# Isolated_I2C_Bus_Repeater.net
KiCad netlist of a schematic drawn in EAGLE
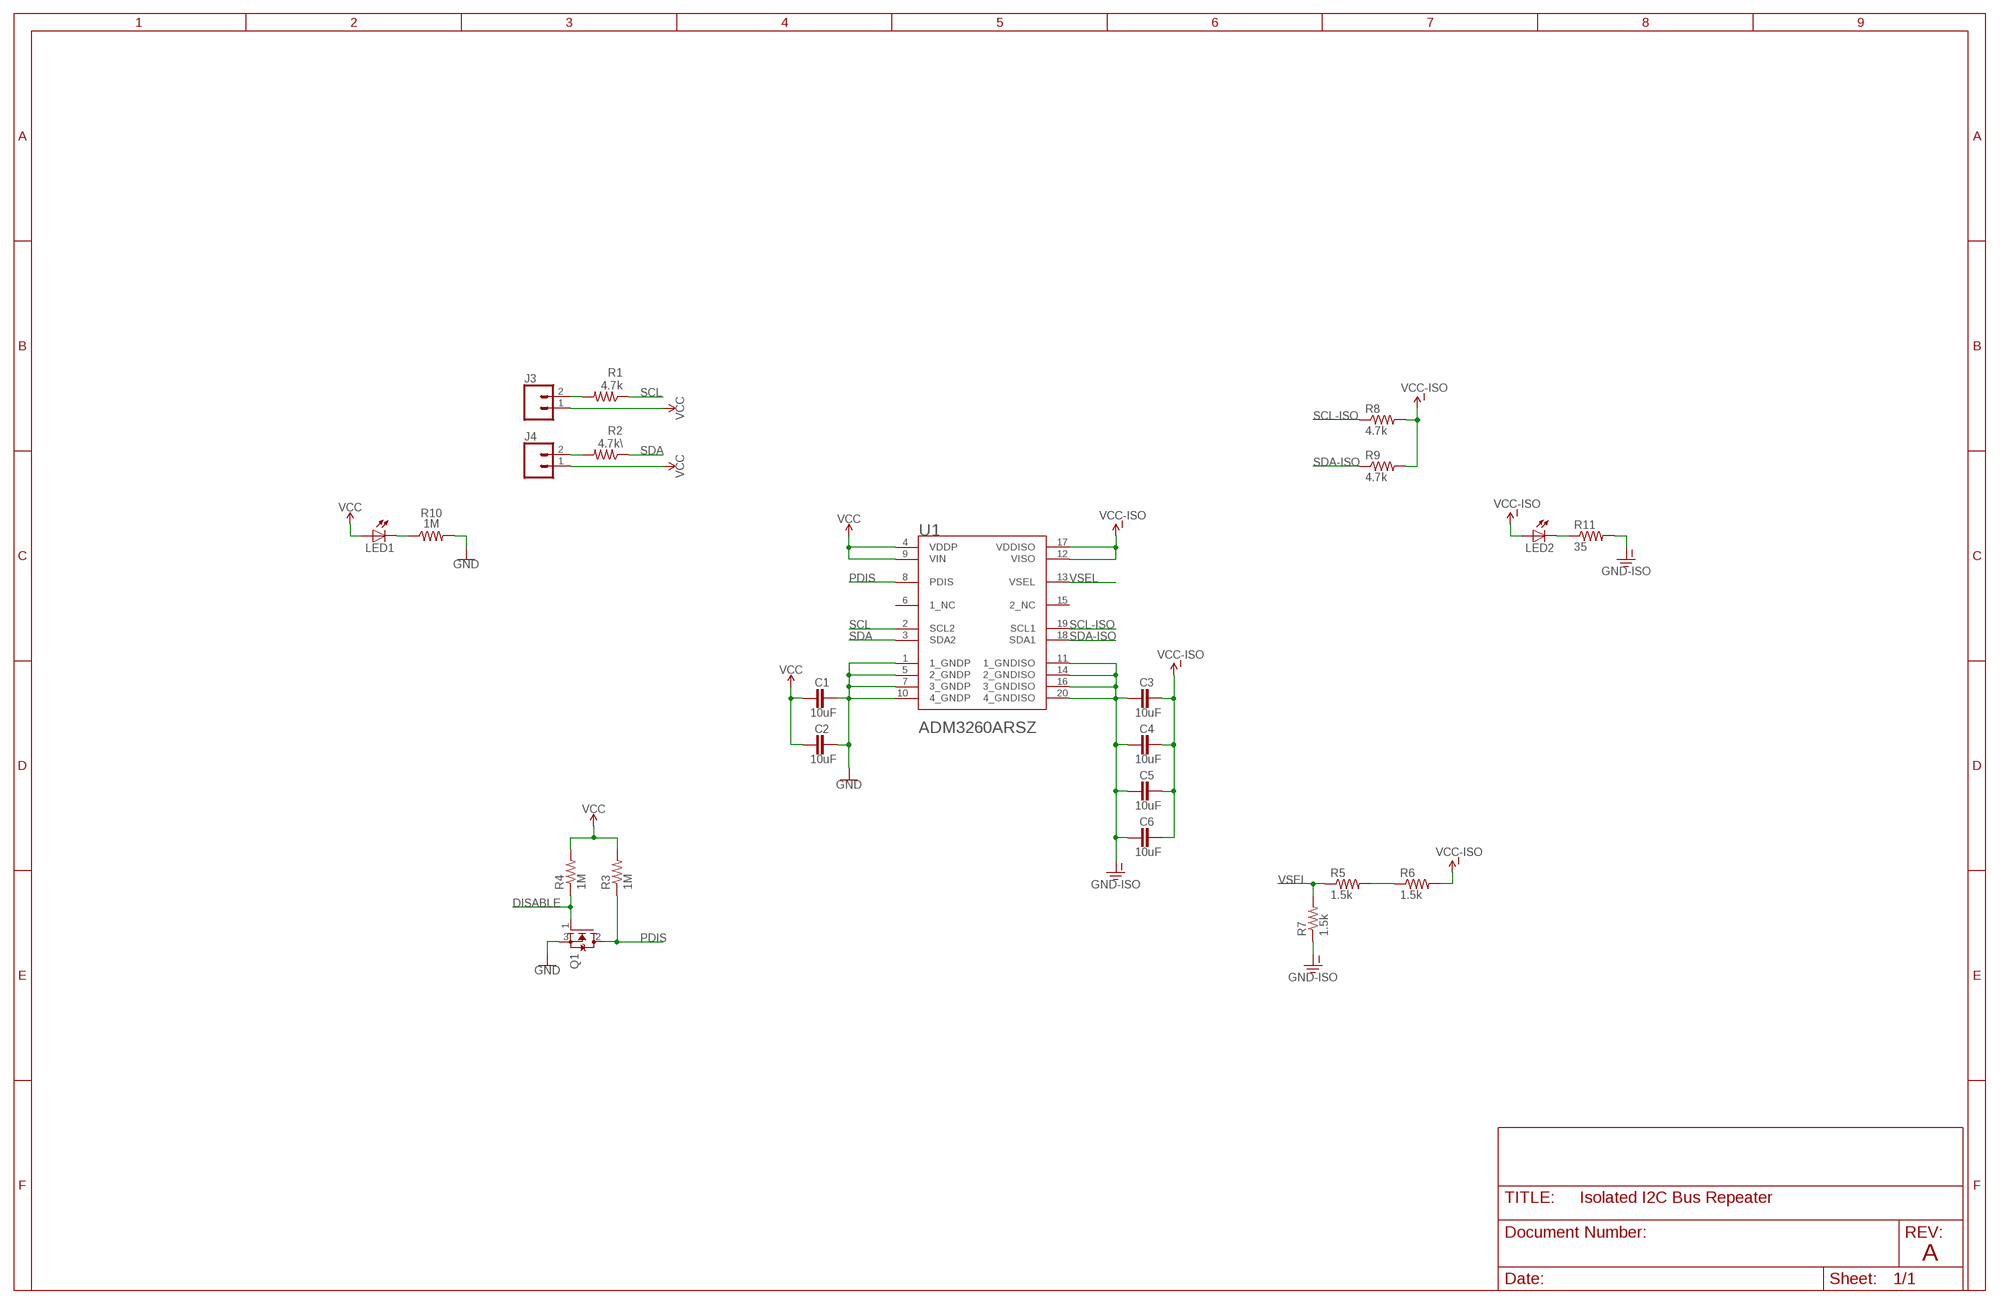
[diagram p0: schematic, sheet 1]

(export (version "E")
  (design (tool "Eeschema 10.0.6"))
  (components
    (comp (ref "C1")
      (value "10uF")
      (footprint "eagle-import:CAP-PTH-2.54")
      (libsource (lib "eagle-import") (part "22PF-PTH-2.54MM-200V-5%"))
    )
    (comp (ref "C2")
      (value "10uF")
      (footprint "eagle-import:CAP-PTH-2.54")
      (libsource (lib "eagle-import") (part "22PF-PTH-2.54MM-200V-5%"))
    )
    (comp (ref "C3")
      (value "10uF")
      (footprint "eagle-import:CAP-PTH-2.54")
      (libsource (lib "eagle-import") (part "22PF-PTH-2.54MM-200V-5%"))
    )
    (comp (ref "C4")
      (value "10uF")
      (footprint "eagle-import:CAP-PTH-2.54")
      (libsource (lib "eagle-import") (part "22PF-PTH-2.54MM-200V-5%"))
    )
    (comp (ref "C5")
      (value "10uF")
      (footprint "eagle-import:CAP-PTH-2.54")
      (libsource (lib "eagle-import") (part "22PF-PTH-2.54MM-200V-5%"))
    )
    (comp (ref "C6")
      (value "10uF")
      (footprint "eagle-import:CAP-PTH-2.54")
      (libsource (lib "eagle-import") (part "22PF-PTH-2.54MM-200V-5%"))
    )
    (comp (ref "J3")
      (value "CONN_02")
      (footprint "eagle-import:1X02")
      (libsource (lib "eagle-import") (part "CONN_02"))
    )
    (comp (ref "J4")
      (value "CONN_02")
      (footprint "eagle-import:1X02")
      (libsource (lib "eagle-import") (part "CONN_02"))
    )
    (comp (ref "LED1")
      (value "LED5MM")
      (footprint "eagle-import:LED5MM")
      (libsource (lib "eagle-import") (part "LED5MM"))
    )
    (comp (ref "LED2")
      (value "LED5MM")
      (footprint "eagle-import:LED5MM")
      (libsource (lib "eagle-import") (part "LED5MM"))
    )
    (comp (ref "Q1")
      (value "MOSFET-NGDS_TO220V")
      (footprint "eagle-import:TO220V")
      (libsource (lib "eagle-import") (part "MOSFET-NGDS_TO220V"))
    )
    (comp (ref "R1")
      (value "4.7k")
      (footprint "eagle-import:AXIAL-0.3")
      (libsource (lib "eagle-import") (part "1MOHM-HORIZ-1/4W-5%"))
    )
    (comp (ref "R2")
      (value "4.7k\\")
      (footprint "eagle-import:AXIAL-0.3")
      (libsource (lib "eagle-import") (part "1MOHM-HORIZ-1/4W-5%"))
    )
    (comp (ref "R3")
      (value "1M")
      (footprint "eagle-import:AXIAL-0.3")
      (libsource (lib "eagle-import") (part "1MOHM-HORIZ-1/4W-5%"))
    )
    (comp (ref "R4")
      (value "1M")
      (footprint "eagle-import:AXIAL-0.3")
      (libsource (lib "eagle-import") (part "1MOHM-HORIZ-1/4W-5%"))
    )
    (comp (ref "R5")
      (value "1.5k")
      (footprint "eagle-import:AXIAL-0.3")
      (libsource (lib "eagle-import") (part "1MOHM-HORIZ-1/4W-5%"))
    )
    (comp (ref "R6")
      (value "1.5k")
      (footprint "eagle-import:AXIAL-0.3")
      (libsource (lib "eagle-import") (part "1MOHM-HORIZ-1/4W-5%"))
    )
    (comp (ref "R7")
      (value "1.5k")
      (footprint "eagle-import:AXIAL-0.3")
      (libsource (lib "eagle-import") (part "1MOHM-HORIZ-1/4W-5%"))
    )
    (comp (ref "R8")
      (value "4.7k")
      (footprint "eagle-import:AXIAL-0.3")
      (libsource (lib "eagle-import") (part "1MOHM-HORIZ-1/4W-5%"))
    )
    (comp (ref "R9")
      (value "4.7k")
      (footprint "eagle-import:AXIAL-0.3")
      (libsource (lib "eagle-import") (part "1MOHM-HORIZ-1/4W-5%"))
    )
    (comp (ref "R10")
      (value "1M")
      (footprint "eagle-import:AXIAL-0.3")
      (libsource (lib "eagle-import") (part "1MOHM-HORIZ-1/4W-5%"))
    )
    (comp (ref "R11")
      (value "35")
      (footprint "eagle-import:AXIAL-0.3")
      (libsource (lib "eagle-import") (part "1MOHM-HORIZ-1/4W-5%"))
    )
    (comp (ref "U1")
      (value "ANALOG_DEVICES_INC_ADM3260ARSZANALOG_DEVICES_INC_ADM3260ARSZ_0_0")
      (footprint "eagle-import:ANALOG_DEVICES_INC_ADM3260ARSZ_0")
      (fields
        (field (name "DIGIKEY_PART_NUMBER") "ADM3260ARSZ-ND")
        (field (name "MF") "Analog Devices Inc")
        (field (name "MOUSER_PART_NUMBER") "584-ADM3260ARSZ")
      )
      (libsource (lib "eagle-import") (part "ANALOG_DEVICES_INC_ADM3260ARSZANALOG_DEVICES_INC_ADM3260ARSZ_0_0"))
    )
  )
  (nets
    (net (code "1") (name "/DISABLE") (class "Default")
      (node (ref "Q1") (pin "1") (pinfunction "G_1") (pintype "bidirectional"))
      (node (ref "R4") (pin "P$1") (pinfunction "1_P$1") (pintype "passive"))
    )
    (net (code "2") (name "/PDIS") (class "Default")
      (node (ref "Q1") (pin "2") (pinfunction "D_2") (pintype "bidirectional"))
      (node (ref "R3") (pin "P$1") (pinfunction "1_P$1") (pintype "passive"))
      (node (ref "U1") (pin "8") (pinfunction "PDIS_8") (pintype "input"))
    )
    (net (code "3") (name "/SCL") (class "Default")
      (node (ref "R1") (pin "P$1") (pinfunction "1_P$1") (pintype "passive"))
      (node (ref "U1") (pin "2") (pinfunction "SCL2_2") (pintype "bidirectional"))
    )
    (net (code "4") (name "/SCL-ISO") (class "Default")
      (node (ref "R8") (pin "P$1") (pinfunction "1_P$1") (pintype "passive"))
      (node (ref "U1") (pin "19") (pinfunction "SCL1_19") (pintype "bidirectional"))
    )
    (net (code "5") (name "/SDA") (class "Default")
      (node (ref "R2") (pin "P$1") (pinfunction "1_P$1") (pintype "passive"))
      (node (ref "U1") (pin "3") (pinfunction "SDA2_3") (pintype "bidirectional"))
    )
    (net (code "6") (name "/SDA-ISO") (class "Default")
      (node (ref "R9") (pin "P$1") (pinfunction "1_P$1") (pintype "passive"))
      (node (ref "U1") (pin "18") (pinfunction "SDA1_18") (pintype "bidirectional"))
    )
    (net (code "7") (name "/VSEL") (class "Default")
      (node (ref "R5") (pin "P$1") (pinfunction "1_P$1") (pintype "passive"))
      (node (ref "R7") (pin "P$2") (pinfunction "2_P$2") (pintype "passive"))
      (node (ref "U1") (pin "13") (pinfunction "VSEL_13") (pintype "input"))
    )
    (net (code "8") (name "GND") (class "Default")
      (node (ref "C1") (pin "2") (pinfunction "2_2") (pintype "passive"))
      (node (ref "C2") (pin "2") (pinfunction "2_2") (pintype "passive"))
      (node (ref "Q1") (pin "3") (pinfunction "S_3") (pintype "bidirectional"))
      (node (ref "R10") (pin "P$2") (pinfunction "2_P$2") (pintype "passive"))
      (node (ref "U1") (pin "1") (pinfunction "1_GNDP_1") (pintype "power_in"))
      (node (ref "U1") (pin "10") (pinfunction "4_GNDP_10") (pintype "power_in"))
      (node (ref "U1") (pin "5") (pinfunction "2_GNDP_5") (pintype "power_in"))
      (node (ref "U1") (pin "7") (pinfunction "3_GNDP_7") (pintype "power_in"))
    )
    (net (code "9") (name "GND-ISO") (class "Default")
      (node (ref "C3") (pin "1") (pinfunction "1_1") (pintype "passive"))
      (node (ref "C4") (pin "1") (pinfunction "1_1") (pintype "passive"))
      (node (ref "C5") (pin "1") (pinfunction "1_1") (pintype "passive"))
      (node (ref "C6") (pin "1") (pinfunction "1_1") (pintype "passive"))
      (node (ref "R11") (pin "P$2") (pinfunction "2_P$2") (pintype "passive"))
      (node (ref "R7") (pin "P$1") (pinfunction "1_P$1") (pintype "passive"))
      (node (ref "U1") (pin "11") (pinfunction "1_GNDISO_11") (pintype "power_in"))
      (node (ref "U1") (pin "14") (pinfunction "2_GNDISO_14") (pintype "power_in"))
      (node (ref "U1") (pin "16") (pinfunction "3_GNDISO_16") (pintype "power_in"))
      (node (ref "U1") (pin "20") (pinfunction "4_GNDISO_20") (pintype "power_in"))
    )
    (net (code "10") (name "Net-(LED1-C)") (class "Default")
      (node (ref "LED1") (pin "K") (pinfunction "C_K") (pintype "passive"))
      (node (ref "R10") (pin "P$1") (pinfunction "1_P$1") (pintype "passive"))
    )
    (net (code "11") (name "Net-(LED2-C)") (class "Default")
      (node (ref "LED2") (pin "K") (pinfunction "C_K") (pintype "passive"))
      (node (ref "R11") (pin "P$1") (pinfunction "1_P$1") (pintype "passive"))
    )
    (net (code "12") (name "Net-(R1-2)") (class "Default")
      (node (ref "J3") (pin "2") (pinfunction "2_2") (pintype "passive"))
      (node (ref "R1") (pin "P$2") (pinfunction "2_P$2") (pintype "passive"))
    )
    (net (code "13") (name "Net-(R2-2)") (class "Default")
      (node (ref "J4") (pin "2") (pinfunction "2_2") (pintype "passive"))
      (node (ref "R2") (pin "P$2") (pinfunction "2_P$2") (pintype "passive"))
    )
    (net (code "14") (name "Net-(R5-2)") (class "Default")
      (node (ref "R5") (pin "P$2") (pinfunction "2_P$2") (pintype "passive"))
      (node (ref "R6") (pin "P$1") (pinfunction "1_P$1") (pintype "passive"))
    )
    (net (code "15") (name "VCC") (class "Default")
      (node (ref "C1") (pin "1") (pinfunction "1_1") (pintype "passive"))
      (node (ref "C2") (pin "1") (pinfunction "1_1") (pintype "passive"))
      (node (ref "J3") (pin "1") (pinfunction "1_1") (pintype "passive"))
      (node (ref "J4") (pin "1") (pinfunction "1_1") (pintype "passive"))
      (node (ref "LED1") (pin "A") (pinfunction "A_A") (pintype "passive"))
      (node (ref "R3") (pin "P$2") (pinfunction "2_P$2") (pintype "passive"))
      (node (ref "R4") (pin "P$2") (pinfunction "2_P$2") (pintype "passive"))
      (node (ref "U1") (pin "4") (pinfunction "VDDP_4") (pintype "power_in"))
      (node (ref "U1") (pin "9") (pinfunction "VIN_9") (pintype "power_in"))
    )
    (net (code "16") (name "VCC-ISO") (class "Default")
      (node (ref "C3") (pin "2") (pinfunction "2_2") (pintype "passive"))
      (node (ref "C4") (pin "2") (pinfunction "2_2") (pintype "passive"))
      (node (ref "C5") (pin "2") (pinfunction "2_2") (pintype "passive"))
      (node (ref "C6") (pin "2") (pinfunction "2_2") (pintype "passive"))
      (node (ref "LED2") (pin "A") (pinfunction "A_A") (pintype "passive"))
      (node (ref "R6") (pin "P$2") (pinfunction "2_P$2") (pintype "passive"))
      (node (ref "R8") (pin "P$2") (pinfunction "2_P$2") (pintype "passive"))
      (node (ref "R9") (pin "P$2") (pinfunction "2_P$2") (pintype "passive"))
      (node (ref "U1") (pin "12") (pinfunction "VISO_12") (pintype "power_in"))
      (node (ref "U1") (pin "17") (pinfunction "VDDISO_17") (pintype "power_in"))
    )
    (net (code "17") (name "unconnected-(U1-1_NC-Pad6)") (class "Default")
      (node (ref "U1") (pin "6") (pinfunction "1_NC_6") (pintype "passive"))
    )
    (net (code "18") (name "unconnected-(U1-2_NC-Pad15)") (class "Default")
      (node (ref "U1") (pin "15") (pinfunction "2_NC_15") (pintype "passive"))
    )
  )
)
